# Arduino-HC05.net
KiCad netlist of a schematic drawn in EAGLE
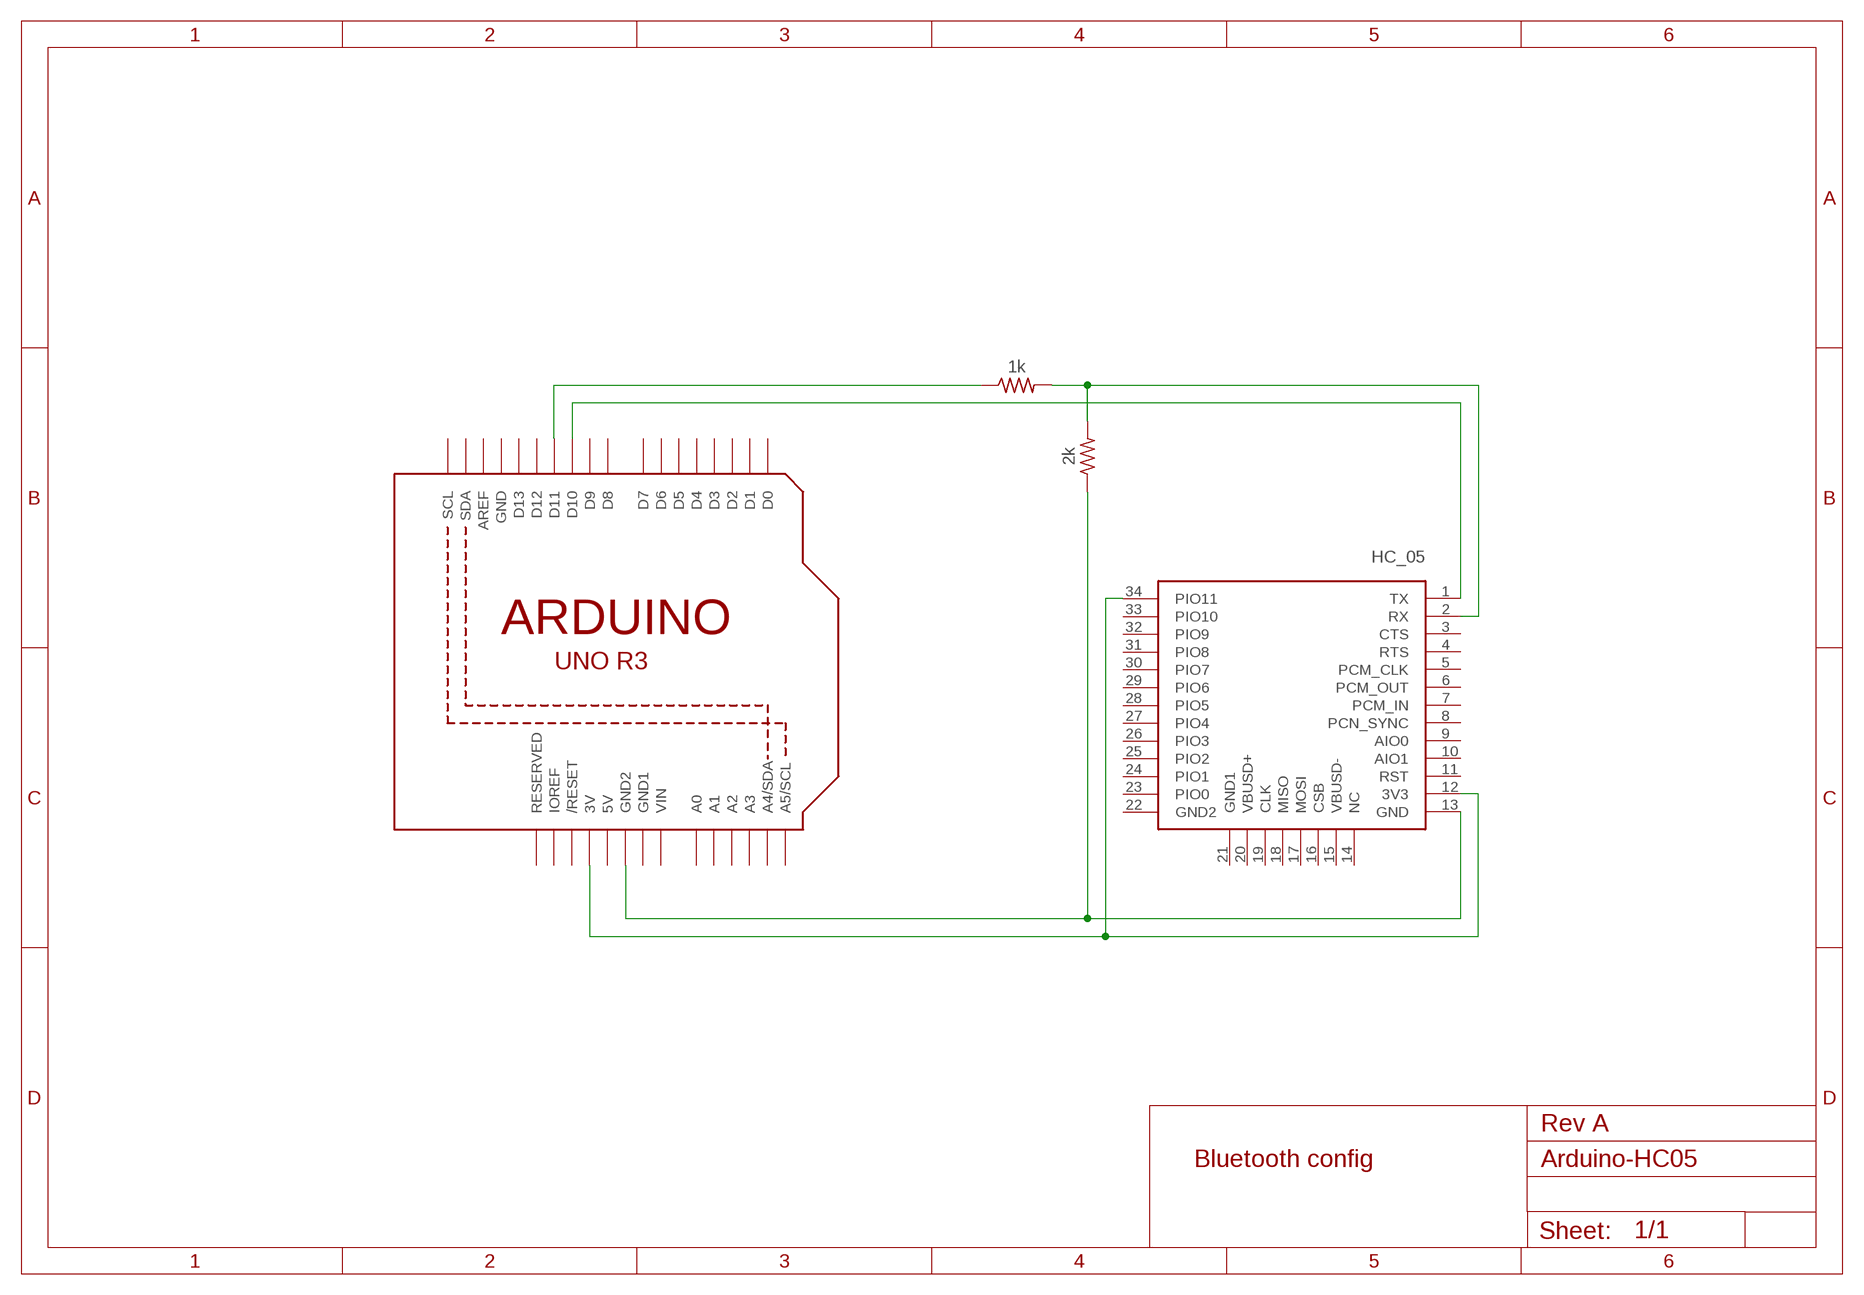
[diagram p0: schematic, sheet 1]

(export (version "E")
  (design (tool "Eeschema 10.0.6"))
  (components
    (comp (ref "R1")
      (value "1k")
      (footprint "eagle-import:0207_15")
      (libsource (lib "eagle-import") (part "R-US_0207/15"))
    )
    (comp (ref "R2")
      (value "2k")
      (footprint "eagle-import:0207_15")
      (libsource (lib "eagle-import") (part "R-US_0207/15"))
    )
    (comp (ref "U1")
      (value "ARDUINOR3-BPLACE")
      (footprint "eagle-import:ARDUINOR3-BPLACE")
      (libsource (lib "eagle-import") (part "ARDUINOR3-BPLACE"))
    )
    (comp (ref "U2")
      (value "HC_05")
      (footprint "eagle-import:BLUETOOTH_SMD")
      (libsource (lib "eagle-import") (part "HC_05"))
    )
  )
  (nets
    (net (code "1") (name "/5V") (class "Default")
      (node (ref "U1") (pin "5V") (pinfunction "5V_5V") (pintype "power_in"))
    )
    (net (code "2") (name "/GND") (class "Default")
      (node (ref "U1") (pin "GND") (pinfunction "GND_GND") (pintype "power_in"))
    )
    (net (code "3") (name "/GND1") (class "Default")
      (node (ref "U1") (pin "GND1") (pinfunction "GND1_GND1") (pintype "power_in"))
    )
    (net (code "4") (name "/VIN") (class "Default")
      (node (ref "U1") (pin "VIN") (pinfunction "VIN_VIN") (pintype "power_in"))
    )
    (net (code "5") (name "Net-(R1-Pad1)") (class "Default")
      (node (ref "R1") (pin "1") (pinfunction "1_1") (pintype "passive"))
      (node (ref "U1") (pin "D11") (pinfunction "D11_D11") (pintype "bidirectional"))
    )
    (net (code "6") (name "Net-(U2-3V3)") (class "Default")
      (node (ref "U1") (pin "3V") (pinfunction "3V_3V") (pintype "power_in"))
      (node (ref "U2") (pin "12") (pinfunction "3V3_12") (pintype "bidirectional"))
      (node (ref "U2") (pin "34") (pinfunction "PIO11_34") (pintype "bidirectional"))
    )
    (net (code "7") (name "Net-(U2-GND)") (class "Default")
      (node (ref "R2") (pin "1") (pinfunction "1_1") (pintype "passive"))
      (node (ref "U1") (pin "GND2") (pinfunction "GND2_GND2") (pintype "power_in"))
      (node (ref "U2") (pin "13") (pinfunction "GND_13") (pintype "bidirectional"))
    )
    (net (code "8") (name "Net-(U2-RX)") (class "Default")
      (node (ref "R1") (pin "2") (pinfunction "2_2") (pintype "passive"))
      (node (ref "R2") (pin "2") (pinfunction "2_2") (pintype "passive"))
      (node (ref "U2") (pin "2") (pinfunction "RX_2") (pintype "bidirectional"))
    )
    (net (code "9") (name "Net-(U2-TX)") (class "Default")
      (node (ref "U1") (pin "D10") (pinfunction "D10_D10") (pintype "bidirectional"))
      (node (ref "U2") (pin "1") (pinfunction "TX_1") (pintype "bidirectional"))
    )
    (net (code "10") (name "unconnected-(U1-A4{slash}SDA-PadA4)") (class "Default")
      (node (ref "U1") (pin "A4") (pinfunction "A4/SDA_A4") (pintype "bidirectional"))
    )
    (net (code "11") (name "unconnected-(U1-A5{slash}SCL-PadA5)") (class "Default")
      (node (ref "U1") (pin "A5") (pinfunction "A5/SCL_A5") (pintype "bidirectional"))
    )
    (net (code "12") (name "unconnected-(U1-PadA0)") (class "Default")
      (node (ref "U1") (pin "A0") (pinfunction "A0_A0") (pintype "bidirectional"))
    )
    (net (code "13") (name "unconnected-(U1-PadA1)") (class "Default")
      (node (ref "U1") (pin "A1") (pinfunction "A1_A1") (pintype "bidirectional"))
    )
    (net (code "14") (name "unconnected-(U1-PadA2)") (class "Default")
      (node (ref "U1") (pin "A2") (pinfunction "A2_A2") (pintype "bidirectional"))
    )
    (net (code "15") (name "unconnected-(U1-PadA3)") (class "Default")
      (node (ref "U1") (pin "A3") (pinfunction "A3_A3") (pintype "bidirectional"))
    )
    (net (code "16") (name "unconnected-(U1-PadAREF)") (class "Default")
      (node (ref "U1") (pin "AREF") (pinfunction "AREF_AREF") (pintype "bidirectional"))
    )
    (net (code "17") (name "unconnected-(U1-PadD0)") (class "Default")
      (node (ref "U1") (pin "D0") (pinfunction "D0_D0") (pintype "bidirectional"))
    )
    (net (code "18") (name "unconnected-(U1-PadD1)") (class "Default")
      (node (ref "U1") (pin "D1") (pinfunction "D1_D1") (pintype "bidirectional"))
    )
    (net (code "19") (name "unconnected-(U1-PadD2)") (class "Default")
      (node (ref "U1") (pin "D2") (pinfunction "D2_D2") (pintype "bidirectional"))
    )
    (net (code "20") (name "unconnected-(U1-PadD3)") (class "Default")
      (node (ref "U1") (pin "D3") (pinfunction "D3_D3") (pintype "bidirectional"))
    )
    (net (code "21") (name "unconnected-(U1-PadD4)") (class "Default")
      (node (ref "U1") (pin "D4") (pinfunction "D4_D4") (pintype "bidirectional"))
    )
    (net (code "22") (name "unconnected-(U1-PadD5)") (class "Default")
      (node (ref "U1") (pin "D5") (pinfunction "D5_D5") (pintype "bidirectional"))
    )
    (net (code "23") (name "unconnected-(U1-PadD6)") (class "Default")
      (node (ref "U1") (pin "D6") (pinfunction "D6_D6") (pintype "bidirectional"))
    )
    (net (code "24") (name "unconnected-(U1-PadD7)") (class "Default")
      (node (ref "U1") (pin "D7") (pinfunction "D7_D7") (pintype "bidirectional"))
    )
    (net (code "25") (name "unconnected-(U1-PadD8)") (class "Default")
      (node (ref "U1") (pin "D8") (pinfunction "D8_D8") (pintype "bidirectional"))
    )
    (net (code "26") (name "unconnected-(U1-PadD9)") (class "Default")
      (node (ref "U1") (pin "D9") (pinfunction "D9_D9") (pintype "bidirectional"))
    )
    (net (code "27") (name "unconnected-(U1-PadD12)") (class "Default")
      (node (ref "U1") (pin "D12") (pinfunction "D12_D12") (pintype "bidirectional"))
    )
    (net (code "28") (name "unconnected-(U1-PadD13)") (class "Default")
      (node (ref "U1") (pin "D13") (pinfunction "D13_D13") (pintype "bidirectional"))
    )
    (net (code "29") (name "unconnected-(U1-PadIOREF)") (class "Default")
      (node (ref "U1") (pin "IOREF") (pinfunction "IOREF_IOREF") (pintype "output"))
    )
    (net (code "30") (name "unconnected-(U1-PadRESERVED)") (class "Default")
      (node (ref "U1") (pin "RESERVED") (pinfunction "RESERVED_RESERVED") (pintype "no_connect"))
    )
    (net (code "31") (name "unconnected-(U1-PadSCL)") (class "Default")
      (node (ref "U1") (pin "SCL") (pinfunction "SCL_SCL") (pintype "bidirectional"))
    )
    (net (code "32") (name "unconnected-(U1-PadSDA)") (class "Default")
      (node (ref "U1") (pin "SDA") (pinfunction "SDA_SDA") (pintype "bidirectional"))
    )
    (net (code "33") (name "unconnected-(U1-{slash}RESET-PadRESET)") (class "Default")
      (node (ref "U1") (pin "RESET") (pinfunction "/RESET_RESET") (pintype "bidirectional"))
    )
    (net (code "34") (name "unconnected-(U2-AIO0-Pad9)") (class "Default")
      (node (ref "U2") (pin "9") (pinfunction "AIO0_9") (pintype "bidirectional"))
    )
    (net (code "35") (name "unconnected-(U2-AIO1-Pad10)") (class "Default")
      (node (ref "U2") (pin "10") (pinfunction "AIO1_10") (pintype "bidirectional"))
    )
    (net (code "36") (name "unconnected-(U2-CLK-Pad19)") (class "Default")
      (node (ref "U2") (pin "19") (pinfunction "CLK_19") (pintype "bidirectional"))
    )
    (net (code "37") (name "unconnected-(U2-CSB-Pad16)") (class "Default")
      (node (ref "U2") (pin "16") (pinfunction "CSB_16") (pintype "bidirectional"))
    )
    (net (code "38") (name "unconnected-(U2-CTS-Pad3)") (class "Default")
      (node (ref "U2") (pin "3") (pinfunction "CTS_3") (pintype "bidirectional"))
    )
    (net (code "39") (name "unconnected-(U2-GND1-Pad21)") (class "Default")
      (node (ref "U2") (pin "21") (pinfunction "GND1_21") (pintype "bidirectional"))
    )
    (net (code "40") (name "unconnected-(U2-GND2-Pad22)") (class "Default")
      (node (ref "U2") (pin "22") (pinfunction "GND2_22") (pintype "bidirectional"))
    )
    (net (code "41") (name "unconnected-(U2-MISO-Pad18)") (class "Default")
      (node (ref "U2") (pin "18") (pinfunction "MISO_18") (pintype "bidirectional"))
    )
    (net (code "42") (name "unconnected-(U2-MOSI-Pad17)") (class "Default")
      (node (ref "U2") (pin "17") (pinfunction "MOSI_17") (pintype "bidirectional"))
    )
    (net (code "43") (name "unconnected-(U2-NC-Pad14)") (class "Default")
      (node (ref "U2") (pin "14") (pinfunction "NC_14") (pintype "bidirectional"))
    )
    (net (code "44") (name "unconnected-(U2-PCM_CLK-Pad5)") (class "Default")
      (node (ref "U2") (pin "5") (pinfunction "PCM_CLK_5") (pintype "bidirectional"))
    )
    (net (code "45") (name "unconnected-(U2-PCM_IN-Pad7)") (class "Default")
      (node (ref "U2") (pin "7") (pinfunction "PCM_IN_7") (pintype "bidirectional"))
    )
    (net (code "46") (name "unconnected-(U2-PCM_OUT-Pad6)") (class "Default")
      (node (ref "U2") (pin "6") (pinfunction "PCM_OUT_6") (pintype "bidirectional"))
    )
    (net (code "47") (name "unconnected-(U2-PCN_SYNC-Pad8)") (class "Default")
      (node (ref "U2") (pin "8") (pinfunction "PCN_SYNC_8") (pintype "bidirectional"))
    )
    (net (code "48") (name "unconnected-(U2-PIO0-Pad23)") (class "Default")
      (node (ref "U2") (pin "23") (pinfunction "PIO0_23") (pintype "bidirectional"))
    )
    (net (code "49") (name "unconnected-(U2-PIO1-Pad24)") (class "Default")
      (node (ref "U2") (pin "24") (pinfunction "PIO1_24") (pintype "bidirectional"))
    )
    (net (code "50") (name "unconnected-(U2-PIO2-Pad25)") (class "Default")
      (node (ref "U2") (pin "25") (pinfunction "PIO2_25") (pintype "bidirectional"))
    )
    (net (code "51") (name "unconnected-(U2-PIO3-Pad26)") (class "Default")
      (node (ref "U2") (pin "26") (pinfunction "PIO3_26") (pintype "bidirectional"))
    )
    (net (code "52") (name "unconnected-(U2-PIO4-Pad27)") (class "Default")
      (node (ref "U2") (pin "27") (pinfunction "PIO4_27") (pintype "bidirectional"))
    )
    (net (code "53") (name "unconnected-(U2-PIO5-Pad28)") (class "Default")
      (node (ref "U2") (pin "28") (pinfunction "PIO5_28") (pintype "bidirectional"))
    )
    (net (code "54") (name "unconnected-(U2-PIO6-Pad29)") (class "Default")
      (node (ref "U2") (pin "29") (pinfunction "PIO6_29") (pintype "bidirectional"))
    )
    (net (code "55") (name "unconnected-(U2-PIO7-Pad30)") (class "Default")
      (node (ref "U2") (pin "30") (pinfunction "PIO7_30") (pintype "bidirectional"))
    )
    (net (code "56") (name "unconnected-(U2-PIO8-Pad31)") (class "Default")
      (node (ref "U2") (pin "31") (pinfunction "PIO8_31") (pintype "bidirectional"))
    )
    (net (code "57") (name "unconnected-(U2-PIO9-Pad32)") (class "Default")
      (node (ref "U2") (pin "32") (pinfunction "PIO9_32") (pintype "bidirectional"))
    )
    (net (code "58") (name "unconnected-(U2-PIO10-Pad33)") (class "Default")
      (node (ref "U2") (pin "33") (pinfunction "PIO10_33") (pintype "bidirectional"))
    )
    (net (code "59") (name "unconnected-(U2-RST-Pad11)") (class "Default")
      (node (ref "U2") (pin "11") (pinfunction "RST_11") (pintype "bidirectional"))
    )
    (net (code "60") (name "unconnected-(U2-RTS-Pad4)") (class "Default")
      (node (ref "U2") (pin "4") (pinfunction "RTS_4") (pintype "bidirectional"))
    )
    (net (code "61") (name "unconnected-(U2-VBUSD+-Pad20)") (class "Default")
      (node (ref "U2") (pin "20") (pinfunction "VBUSD+_20") (pintype "bidirectional"))
    )
    (net (code "62") (name "unconnected-(U2-VBUSD--Pad15)") (class "Default")
      (node (ref "U2") (pin "15") (pinfunction "VBUSD-_15") (pintype "bidirectional"))
    )
  )
)
